# ext_supply.net
KiCad netlist of a schematic drawn in Altium Designer
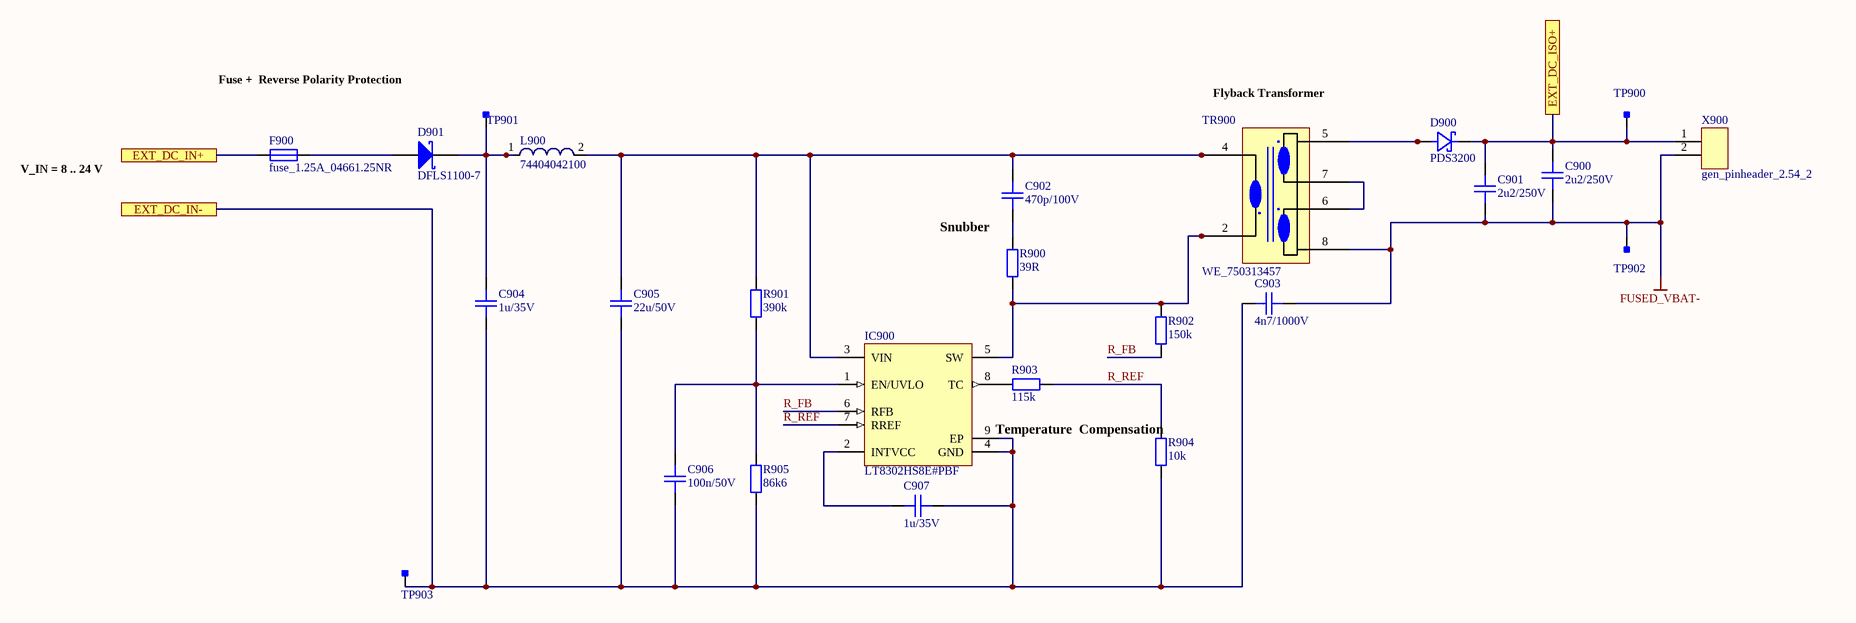
[diagram p0: ext_supply.SchDoc]

(export (version "E")
  (design (tool "Eeschema 10.0.6"))
  (components
    (comp (ref "C900")
      (value "2u2/250V")
      (footprint "CAPC2220(5750)230_N")
      (description "MLCC")
      (fields (field (name "PART NUMBER") "gen_C_ceramic_2u2_250V_X7R_2220"))
      (libsource (lib "OE750") (part "C"))
    )
    (comp (ref "C901")
      (value "2u2/250V")
      (footprint "CAPC2220(5750)230_N")
      (description "MLCC")
      (fields (field (name "PART NUMBER") "gen_C_ceramic_2u2_250V_X7R_2220"))
      (libsource (lib "OE750") (part "C"))
    )
    (comp (ref "C902")
      (value "470p/100V")
      (footprint "CAPC2012X14N")
      (description "MLCC")
      (fields (field (name "PART NUMBER") "gen_C_ceramic_470p_100V_X7R_0805"))
      (libsource (lib "OE750") (part "C"))
    )
    (comp (ref "C903")
      (value "4n7/1000V")
      (footprint "CAPC4532X16N")
      (description "MLCC")
      (fields (field (name "PART NUMBER") "gen_C_ceramic_4n7_1000V_X7R_1812"))
      (libsource (lib "OE750") (part "C"))
    )
    (comp (ref "C904")
      (value "1u/35V")
      (footprint "CAPC1608X08N")
      (description "MLCC")
      (fields (field (name "PART NUMBER") "gen_C_ceramic_1u_35V_X7R_0603"))
      (libsource (lib "OE750") (part "C"))
    )
    (comp (ref "C905")
      (value "22u/50V")
      (footprint "CAPC2220(5750)230_N")
      (description "MLCC")
      (fields (field (name "PART NUMBER") "gen_C_ceramic_22u_50V_X7R_2220_stacked"))
      (libsource (lib "OE750") (part "C"))
    )
    (comp (ref "C906")
      (value "100n/50V")
      (footprint "CAPC1608X08N")
      (description "MLCC")
      (fields (field (name "PART NUMBER") "gen_C_ceramic_100n_50V_X7R_0603"))
      (libsource (lib "OE750") (part "C"))
    )
    (comp (ref "C907")
      (value "1u/35V")
      (footprint "CAPC1608X08N")
      (description "MLCC")
      (fields (field (name "PART NUMBER") "gen_C_ceramic_1u_35V_X7R_0603"))
      (libsource (lib "OE750") (part "C"))
    )
    (comp (ref "D900")
      (value "PDS3200")
      (footprint "PowerDI5")
      (description "Schottky Diode 3A 200V 780mV")
      (fields (field (name "PART NUMBER") "PDS3200-13") (field (name "MANUFACTURER") "DIODES Inc"))
      (libsource (lib "OE750") (part "PDS3200"))
    )
    (comp (ref "D901")
      (value "DFLS1100-7")
      (footprint "DIOD-POWERDI123-2_V")
      (fields (field (name "MANUFACTURER") "Diodes Inc"))
      (libsource (lib "Altium Content Vault") (part "DSKY-AK-2"))
    )
    (comp (ref "F900")
      (value "fuse_1.25A_04661.25NR")
      (footprint "LITTLEFUSE_466")
      (description "Fuse, Surface Mount, 466 Series, 1.25 A, 63 VAC, 63 VDC, Very Fast Acting, 1206")
      (fields (field (name "MANUFACTURER") "Littlefuse"))
      (libsource (lib "OE750") (part "R_Fuse"))
    )
    (comp (ref "IC900")
      (value "LT8302HS8E#PBF")
      (footprint "LT-S8E-8_V")
      (fields (field (name "PARTNUMBER") "LT8302"))
      (libsource (lib "Altium Content Vault") (part "LT-LT8302-S8E-8"))
    )
    (comp (ref "L900")
      (value "74404042100")
      (footprint "WE-LQS 4018")
      (description "WE-LQS SMD Power Inductor, L=10 µH")
      (fields (field (name "MANUFACTURER") "Wuerth Elektronik"))
      (libsource (lib "Altium Content Vault") (part "WE-IND-INDUCTOR-2"))
    )
    (comp (ref "R900")
      (value "39R")
      (footprint "RESC2012X05N")
      (description "SMD Resistor 39R 0805")
      (fields (field (name "PART NUMBER") "gen_R_39R_0805") (field (name "TOLERANCE") "1%"))
      (libsource (lib "OE750") (part "R"))
    )
    (comp (ref "R901")
      (value "390k")
      (footprint "RESC1608X05N")
      (description "SMD Resistor 390k 0603")
      (fields (field (name "PART NUMBER") "gen_R_390k_0603") (field (name "TOLERANCE") "1%"))
      (libsource (lib "OE750") (part "R"))
    )
    (comp (ref "R902")
      (value "150k")
      (footprint "RESC1608X05N")
      (description "SMD Resistor 150k 0603")
      (fields (field (name "PART NUMBER") "gen_R_150k_0603") (field (name "TOLERANCE") "1%"))
      (libsource (lib "OE750") (part "R"))
    )
    (comp (ref "R903")
      (value "115k")
      (footprint "RESC1608X05N")
      (description "SMD Resistor 115k 0603")
      (fields (field (name "PART NUMBER") "gen_R_115k_0603") (field (name "TOLERANCE") "1%"))
      (libsource (lib "OE750") (part "R"))
    )
    (comp (ref "R904")
      (value "10k")
      (footprint "RESC1608X05N")
      (description "SMD Resistor 10k 0603")
      (fields (field (name "PART NUMBER") "gen_R_10k_0603") (field (name "TOLERANCE") "1%"))
      (libsource (lib "OE750") (part "R"))
    )
    (comp (ref "R905")
      (value "86k6")
      (footprint "RESC1608X05N")
      (description "SMD Resistor 86k6 0603")
      (fields (field (name "PART NUMBER") "gen_R_86k6_0603") (field (name "TOLERANCE") "1%"))
      (libsource (lib "OE750") (part "R"))
    )
    (comp (ref "TP900")
      (value "Testpoint_Square")
      (footprint "Testpoint_S1")
      (description "Testpoint, square")
      (libsource (lib "OE750") (part "Testpoint_Square"))
    )
    (comp (ref "TP901")
      (value "Testpoint_Square")
      (footprint "Testpoint_S1")
      (description "Testpoint, square")
      (libsource (lib "OE750") (part "Testpoint_Square"))
    )
    (comp (ref "TP902")
      (value "Testpoint_Square")
      (footprint "Testpoint_S1")
      (description "Testpoint, square")
      (libsource (lib "OE750") (part "Testpoint_Square"))
    )
    (comp (ref "TP903")
      (value "Testpoint_Square")
      (footprint "Testpoint_S1")
      (description "Testpoint, square")
      (libsource (lib "OE750") (part "Testpoint_Square"))
    )
    (comp (ref "TR900")
      (value "WE_750313457")
      (footprint "WE_750313457")
      (description "MID-FLYLT Flyback Transformers for Linear Technology")
      (fields (field (name "MANUFACTURER") "Würth Elektronik"))
      (libsource (lib "OE750") (part "WE_750313457"))
    )
    (comp (ref "X900")
      (value "gen_pinheader_2.54_2")
      (footprint "Pinheader_2.54_2")
      (description "Standard Pinheader, THD, gerade, 2.54mm")
      (libsource (lib "OE750") (part "X2"))
    )
  )
  (nets
    (net (code "1") (name "/EXT_DC_IN+") (class "Default")
      (node (ref "F900") (pin "1") (pinfunction "1_1") (pintype "passive"))
    )
    (net (code "2") (name "/EXT_DC_IN-") (class "Default")
      (node (ref "C903") (pin "1") (pinfunction "1_1") (pintype "passive"))
      (node (ref "C904") (pin "2") (pinfunction "2_2") (pintype "passive"))
      (node (ref "C905") (pin "1") (pinfunction "1_1") (pintype "passive"))
      (node (ref "C906") (pin "1") (pinfunction "1_1") (pintype "passive"))
      (node (ref "C907") (pin "1") (pinfunction "1_1") (pintype "passive"))
      (node (ref "IC900") (pin "4") (pinfunction "GND_4") (pintype "power_in"))
      (node (ref "IC900") (pin "9") (pinfunction "EP_9") (pintype "power_in"))
      (node (ref "R904") (pin "1") (pinfunction "1_1") (pintype "passive"))
      (node (ref "R905") (pin "1") (pinfunction "1_1") (pintype "passive"))
      (node (ref "TP903") (pin "1") (pinfunction "1_1") (pintype "passive"))
    )
    (net (code "3") (name "/EXT_DC_ISO+") (class "Default")
      (node (ref "C900") (pin "2") (pinfunction "2_2") (pintype "passive"))
      (node (ref "C901") (pin "2") (pinfunction "2_2") (pintype "passive"))
      (node (ref "D900") (pin "1") (pinfunction "C_1") (pintype "passive"))
      (node (ref "TP900") (pin "1") (pinfunction "1_1") (pintype "passive"))
      (node (ref "X900") (pin "1") (pintype "passive"))
    )
    (net (code "4") (name "/R_FB") (class "Default")
      (node (ref "IC900") (pin "6") (pinfunction "RFB_6") (pintype "input"))
      (node (ref "R902") (pin "1") (pinfunction "1_1") (pintype "passive"))
    )
    (net (code "5") (name "/R_REF") (class "Default")
      (node (ref "IC900") (pin "7") (pinfunction "RREF_7") (pintype "input"))
      (node (ref "R903") (pin "2") (pinfunction "2_2") (pintype "passive"))
      (node (ref "R904") (pin "2") (pinfunction "2_2") (pintype "passive"))
    )
    (net (code "6") (name "FUSED_VBAT-") (class "Default")
      (node (ref "C900") (pin "1") (pinfunction "1_1") (pintype "passive"))
      (node (ref "C901") (pin "1") (pinfunction "1_1") (pintype "passive"))
      (node (ref "C903") (pin "2") (pinfunction "2_2") (pintype "passive"))
      (node (ref "TP902") (pin "1") (pinfunction "1_1") (pintype "passive"))
      (node (ref "TR900") (pin "8") (pinfunction "8_8") (pintype "passive"))
      (node (ref "X900") (pin "2") (pintype "passive"))
    )
    (net (code "7") (name "Net-(C902-Pad1)") (class "Default")
      (node (ref "C902") (pin "1") (pinfunction "1_1") (pintype "passive"))
      (node (ref "R900") (pin "2") (pinfunction "2_2") (pintype "passive"))
    )
    (net (code "8") (name "Net-(D900-A-Pad2)") (class "Default")
      (node (ref "D900") (pin "2") (pinfunction "A_2") (pintype "passive"))
      (node (ref "D900") (pin "3") (pinfunction "A_3") (pintype "passive"))
      (node (ref "TR900") (pin "5") (pinfunction "5_5") (pintype "passive"))
    )
    (net (code "9") (name "Net-(D901-A)") (class "Default")
      (node (ref "D901") (pin "1") (pinfunction "A_1") (pintype "passive"))
      (node (ref "F900") (pin "2") (pinfunction "2_2") (pintype "passive"))
    )
    (net (code "10") (name "Net-(D901-K)") (class "Default")
      (node (ref "C904") (pin "1") (pinfunction "1_1") (pintype "passive"))
      (node (ref "D901") (pin "2") (pinfunction "K_2") (pintype "passive"))
      (node (ref "L900") (pin "1") (pinfunction "1_1") (pintype "passive"))
      (node (ref "TP901") (pin "1") (pinfunction "1_1") (pintype "passive"))
    )
    (net (code "11") (name "Net-(IC900-EN{slash}UVLO)") (class "Default")
      (node (ref "C906") (pin "2") (pinfunction "2_2") (pintype "passive"))
      (node (ref "IC900") (pin "1") (pinfunction "EN/UVLO_1") (pintype "input"))
      (node (ref "R901") (pin "1") (pinfunction "1_1") (pintype "passive"))
      (node (ref "R905") (pin "2") (pinfunction "2_2") (pintype "passive"))
    )
    (net (code "12") (name "Net-(IC900-INTVCC)") (class "Default")
      (node (ref "C907") (pin "2") (pinfunction "2_2") (pintype "passive"))
      (node (ref "IC900") (pin "2") (pinfunction "INTVCC_2") (pintype "power_in"))
    )
    (net (code "13") (name "Net-(IC900-SW)") (class "Default")
      (node (ref "IC900") (pin "5") (pinfunction "SW_5") (pintype "power_in"))
      (node (ref "R900") (pin "1") (pinfunction "1_1") (pintype "passive"))
      (node (ref "R902") (pin "2") (pinfunction "2_2") (pintype "passive"))
      (node (ref "TR900") (pin "1") (pinfunction "1_1") (pintype "passive"))
      (node (ref "TR900") (pin "2") (pinfunction "2_2") (pintype "passive"))
    )
    (net (code "14") (name "Net-(IC900-TC)") (class "Default")
      (node (ref "IC900") (pin "8") (pinfunction "TC_8") (pintype "output"))
      (node (ref "R903") (pin "1") (pinfunction "1_1") (pintype "passive"))
    )
    (net (code "15") (name "Net-(IC900-VIN)") (class "Default")
      (node (ref "C902") (pin "2") (pinfunction "2_2") (pintype "passive"))
      (node (ref "C905") (pin "2") (pinfunction "2_2") (pintype "passive"))
      (node (ref "IC900") (pin "3") (pinfunction "VIN_3") (pintype "power_in"))
      (node (ref "L900") (pin "2") (pinfunction "2_2") (pintype "passive"))
      (node (ref "R901") (pin "2") (pinfunction "2_2") (pintype "passive"))
      (node (ref "TR900") (pin "3") (pinfunction "3_3") (pintype "passive"))
      (node (ref "TR900") (pin "4") (pinfunction "4_4") (pintype "passive"))
    )
    (net (code "16") (name "Net-(TR900-Pad6)") (class "Default")
      (node (ref "TR900") (pin "6") (pinfunction "6_6") (pintype "passive"))
      (node (ref "TR900") (pin "7") (pinfunction "7_7") (pintype "passive"))
    )
  )
)
